# smartFootballTable_Display.net
KiCad netlist of a schematic drawn in EAGLE
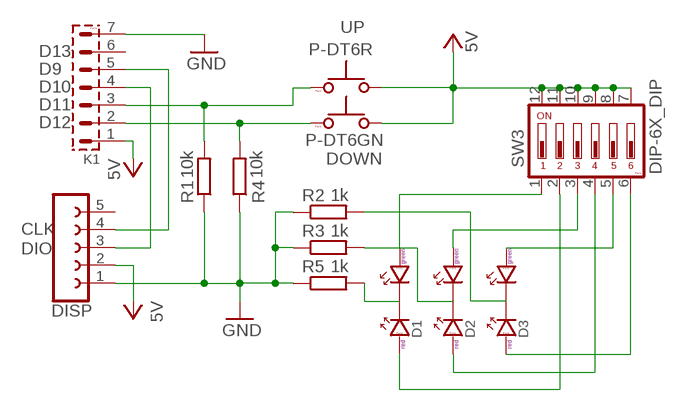
[diagram p0: schematic, sheet 1]

(export (version "E")
  (design (tool "Eeschema 10.0.6"))
  (components
    (comp (ref "D1")
      (value "LED_DUO_3")
      (footprint "eagle-import:LED_3-DUO")
      (libsource (lib "eagle-import") (part "LED_DUO_3"))
    )
    (comp (ref "D2")
      (value "LED_DUO_3")
      (footprint "eagle-import:LED_3-DUO")
      (libsource (lib "eagle-import") (part "LED_DUO_3"))
    )
    (comp (ref "D3")
      (value "LED_DUO_3")
      (footprint "eagle-import:LED_3-DUO")
      (libsource (lib "eagle-import") (part "LED_DUO_3"))
    )
    (comp (ref "DISP")
      (value "FE05W")
      (footprint "eagle-import:FE05W")
      (libsource (lib "eagle-import") (part "FE05W"))
    )
    (comp (ref "DOWN")
      (value "P-DT6GN")
      (footprint "eagle-import:P-DTE6")
      (libsource (lib "eagle-import") (part "P-DT6E"))
    )
    (comp (ref "K1")
      (value "PSH02-07W")
      (footprint "eagle-import:PSH02-07W")
      (libsource (lib "eagle-import") (part "PSH02-07W"))
    )
    (comp (ref "R1")
      (value "10k")
      (footprint "eagle-import:0204_7")
      (libsource (lib "eagle-import") (part "R-EU_0204/7"))
    )
    (comp (ref "R2")
      (value "1k")
      (footprint "eagle-import:0204_7")
      (libsource (lib "eagle-import") (part "R-EU_0204/7"))
    )
    (comp (ref "R3")
      (value "1k")
      (footprint "eagle-import:0204_7")
      (libsource (lib "eagle-import") (part "R-EU_0204/7"))
    )
    (comp (ref "R4")
      (value "10k")
      (footprint "eagle-import:0204_7")
      (libsource (lib "eagle-import") (part "R-EU_0204/7"))
    )
    (comp (ref "R5")
      (value "1k")
      (footprint "eagle-import:0204_7")
      (libsource (lib "eagle-import") (part "R-EU_0204/7"))
    )
    (comp (ref "SW3")
      (value "DIP-6X_DIP")
      (footprint "eagle-import:DIP-6X")
      (libsource (lib "eagle-import") (part "DIP-6X_DIP"))
    )
    (comp (ref "UP")
      (value "P-DT6R")
      (footprint "eagle-import:P-DTE6")
      (libsource (lib "eagle-import") (part "P-DT6E"))
    )
  )
  (nets
    (net (code "1") (name "5V") (class "Default")
      (node (ref "DISP") (pin "2") (pinfunction "2_2") (pintype "passive"))
      (node (ref "DOWN") (pin "2") (pinfunction "2_2") (pintype "passive"))
      (node (ref "K1") (pin "1") (pinfunction "1_1") (pintype "passive"))
      (node (ref "SW3") (pin "10") (pinfunction "10_10") (pintype "passive"))
      (node (ref "SW3") (pin "11") (pinfunction "11_11") (pintype "passive"))
      (node (ref "SW3") (pin "12") (pinfunction "12_12") (pintype "passive"))
      (node (ref "SW3") (pin "7") (pinfunction "7_7") (pintype "passive"))
      (node (ref "SW3") (pin "8") (pinfunction "8_8") (pintype "passive"))
      (node (ref "SW3") (pin "9") (pinfunction "9_9") (pintype "passive"))
      (node (ref "UP") (pin "2") (pinfunction "2_2") (pintype "passive"))
    )
    (net (code "2") (name "GND") (class "Default")
      (node (ref "DISP") (pin "1") (pinfunction "1_1") (pintype "passive"))
      (node (ref "K1") (pin "7") (pinfunction "7_7") (pintype "passive"))
      (node (ref "R1") (pin "1") (pinfunction "1_1") (pintype "passive"))
      (node (ref "R2") (pin "1") (pinfunction "1_1") (pintype "passive"))
      (node (ref "R3") (pin "1") (pinfunction "1_1") (pintype "passive"))
      (node (ref "R4") (pin "1") (pinfunction "1_1") (pintype "passive"))
      (node (ref "R5") (pin "1") (pinfunction "1_1") (pintype "passive"))
    )
    (net (code "3") (name "Net-(D1-PadA1)") (class "Default")
      (node (ref "D1") (pin "A1") (pinfunction "A1_A1") (pintype "passive"))
      (node (ref "SW3") (pin "2") (pinfunction "2_2") (pintype "passive"))
    )
    (net (code "4") (name "Net-(D1-PadA2)") (class "Default")
      (node (ref "D1") (pin "A2") (pinfunction "A2_A2") (pintype "passive"))
      (node (ref "SW3") (pin "1") (pinfunction "1_1") (pintype "passive"))
    )
    (net (code "5") (name "Net-(D1-PadK)") (class "Default")
      (node (ref "D1") (pin "K") (pinfunction "K_K") (pintype "passive"))
      (node (ref "R5") (pin "2") (pinfunction "2_2") (pintype "passive"))
    )
    (net (code "6") (name "Net-(D2-PadA1)") (class "Default")
      (node (ref "D2") (pin "A1") (pinfunction "A1_A1") (pintype "passive"))
      (node (ref "SW3") (pin "4") (pinfunction "4_4") (pintype "passive"))
    )
    (net (code "7") (name "Net-(D2-PadA2)") (class "Default")
      (node (ref "D2") (pin "A2") (pinfunction "A2_A2") (pintype "passive"))
      (node (ref "SW3") (pin "3") (pinfunction "3_3") (pintype "passive"))
    )
    (net (code "8") (name "Net-(D2-PadK)") (class "Default")
      (node (ref "D2") (pin "K") (pinfunction "K_K") (pintype "passive"))
      (node (ref "R3") (pin "2") (pinfunction "2_2") (pintype "passive"))
    )
    (net (code "9") (name "Net-(D3-PadA1)") (class "Default")
      (node (ref "D3") (pin "A1") (pinfunction "A1_A1") (pintype "passive"))
      (node (ref "SW3") (pin "6") (pinfunction "6_6") (pintype "passive"))
    )
    (net (code "10") (name "Net-(D3-PadA2)") (class "Default")
      (node (ref "D3") (pin "A2") (pinfunction "A2_A2") (pintype "passive"))
      (node (ref "SW3") (pin "5") (pinfunction "5_5") (pintype "passive"))
    )
    (net (code "11") (name "Net-(D3-PadK)") (class "Default")
      (node (ref "D3") (pin "K") (pinfunction "K_K") (pintype "passive"))
      (node (ref "R2") (pin "2") (pinfunction "2_2") (pintype "passive"))
    )
    (net (code "12") (name "Net-(DISP-Pad3)") (class "Default")
      (node (ref "DISP") (pin "3") (pinfunction "3_3") (pintype "passive"))
      (node (ref "K1") (pin "4") (pinfunction "4_4") (pintype "passive"))
    )
    (net (code "13") (name "Net-(DISP-Pad4)") (class "Default")
      (node (ref "DISP") (pin "4") (pinfunction "4_4") (pintype "passive"))
      (node (ref "K1") (pin "5") (pinfunction "5_5") (pintype "passive"))
    )
    (net (code "14") (name "Net-(DOWN-Pad1)") (class "Default")
      (node (ref "DOWN") (pin "1") (pinfunction "1_1") (pintype "passive"))
      (node (ref "K1") (pin "2") (pinfunction "2_2") (pintype "passive"))
      (node (ref "R4") (pin "2") (pinfunction "2_2") (pintype "passive"))
    )
    (net (code "15") (name "Net-(K1-Pad3)") (class "Default")
      (node (ref "K1") (pin "3") (pinfunction "3_3") (pintype "passive"))
      (node (ref "R1") (pin "2") (pinfunction "2_2") (pintype "passive"))
      (node (ref "UP") (pin "1") (pinfunction "1_1") (pintype "passive"))
    )
    (net (code "16") (name "unconnected-(DISP-Pad5)") (class "Default")
      (node (ref "DISP") (pin "5") (pinfunction "5_5") (pintype "passive"))
    )
    (net (code "17") (name "unconnected-(DOWN-Pad1A)") (class "Default")
      (node (ref "DOWN") (pin "1A") (pinfunction "1A_1A") (pintype "passive"))
    )
    (net (code "18") (name "unconnected-(DOWN-Pad2A)") (class "Default")
      (node (ref "DOWN") (pin "2A") (pinfunction "2A_2A") (pintype "passive"))
    )
    (net (code "19") (name "unconnected-(K1-Pad6)") (class "Default")
      (node (ref "K1") (pin "6") (pinfunction "6_6") (pintype "passive"))
    )
    (net (code "20") (name "unconnected-(UP-Pad1A)") (class "Default")
      (node (ref "UP") (pin "1A") (pinfunction "1A_1A") (pintype "passive"))
    )
    (net (code "21") (name "unconnected-(UP-Pad2A)") (class "Default")
      (node (ref "UP") (pin "2A") (pinfunction "2A_2A") (pintype "passive"))
    )
  )
)
